# UCube_v2_Led1.net
KiCad netlist of a schematic drawn in EAGLE
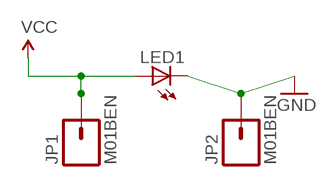
[diagram p0: schematic, sheet 1]

(export (version "E")
  (design (tool "Eeschema 10.0.6"))
  (components
    (comp (ref "JP1")
      (value "M01BEN")
      (footprint "eagle-import:1X01-BEN")
      (libsource (lib "eagle-import") (part "M01BEN"))
    )
    (comp (ref "JP2")
      (value "M01BEN")
      (footprint "eagle-import:1X01-BEN")
      (libsource (lib "eagle-import") (part "M01BEN"))
    )
    (comp (ref "LED1")
      (value "LED5MM")
      (footprint "eagle-import:LED5MM")
      (libsource (lib "eagle-import") (part "LED5MM"))
    )
  )
  (nets
    (net (code "1") (name "GND") (class "Default")
      (node (ref "JP2") (pin "1") (pinfunction "1_1") (pintype "passive"))
      (node (ref "LED1") (pin "K") (pinfunction "C_K") (pintype "passive"))
    )
    (net (code "2") (name "VCC") (class "Default")
      (node (ref "JP1") (pin "1") (pinfunction "1_1") (pintype "passive"))
      (node (ref "LED1") (pin "A") (pinfunction "A_A") (pintype "passive"))
    )
  )
)
